# schematic.net
KiCad netlist of a schematic drawn in EAGLE
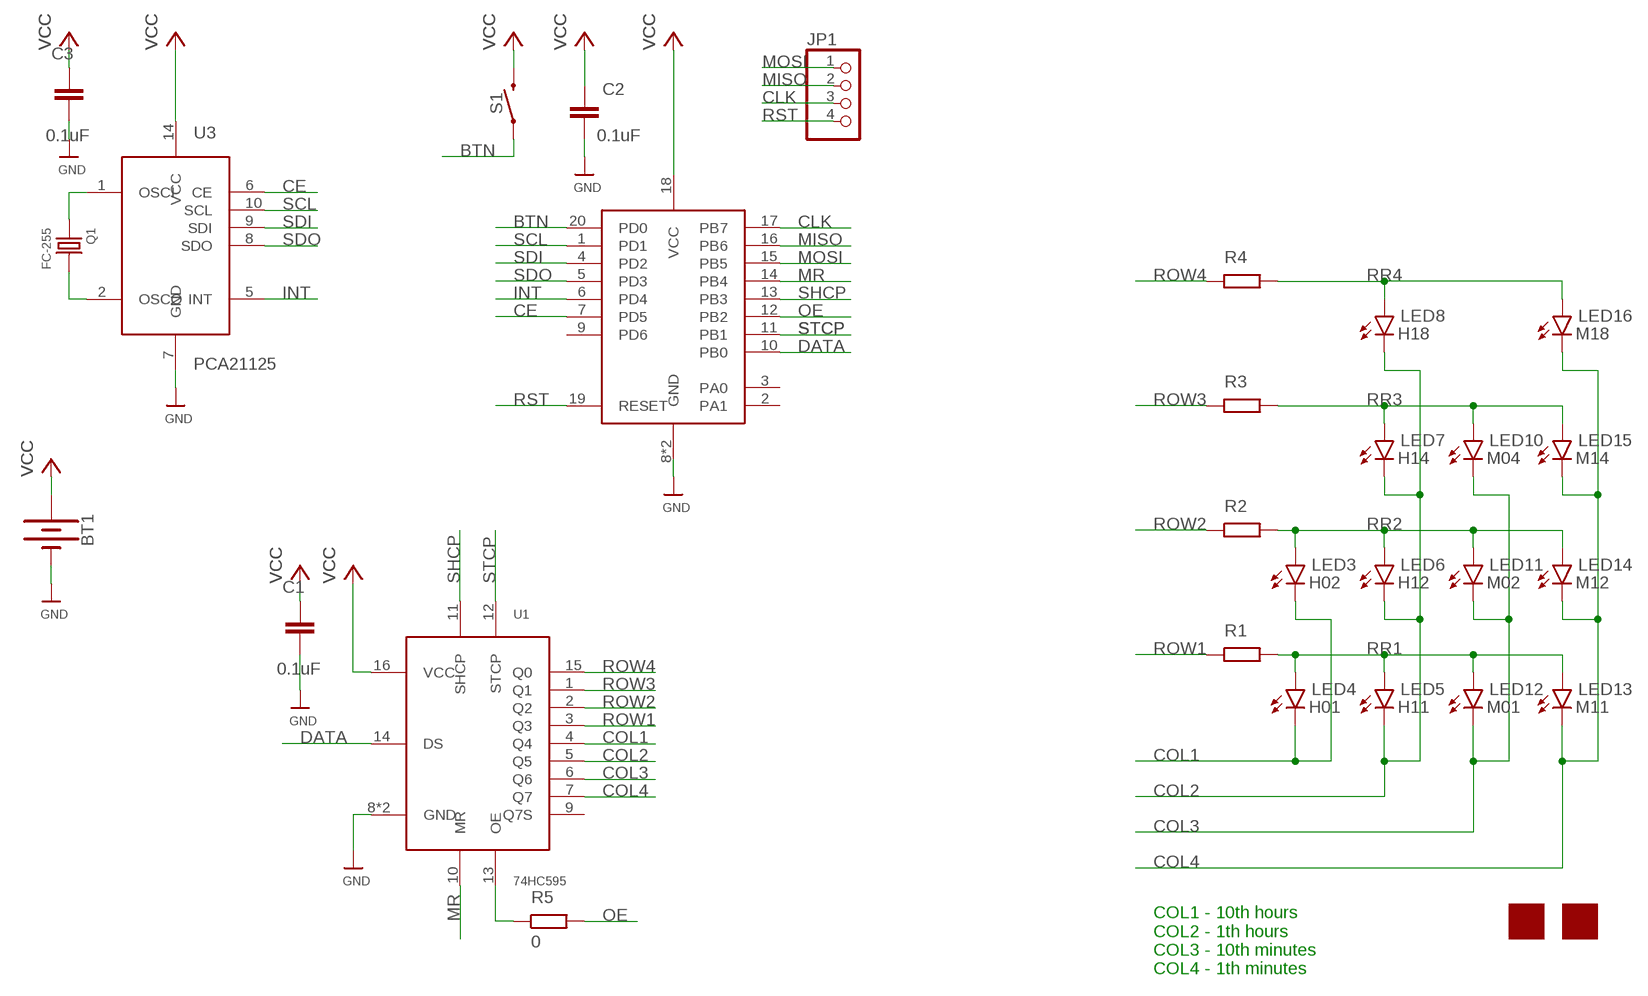
[diagram p0: schematic, sheet 1]

(export (version "E")
  (design (tool "Eeschema 10.0.6"))
  (components
    (comp (ref "BT1")
      (value "BATTERY-12MM_SMD")
      (footprint "eagle-import:BATTCON_12MM")
      (libsource (lib "eagle-import") (part "BATTERY-12MM_SMD"))
    )
    (comp (ref "C1")
      (value "0.1uF")
      (footprint "eagle-import:CAP_0402")
      (fields
        (field (name "DIGIKEY_PART_NUMBER") "311-2076-2-ND")
        (field (name "MANUFACTURER") "Yageo")
        (field (name "MPN") "CC0402CRNPO9BN1R0")
        (field (name "CREATED_BY") "PCBLayout.com")
      )
      (libsource (lib "eagle-import") (part "CC0402CRNPO9BN1R0"))
    )
    (comp (ref "C2")
      (value "0.1uF")
      (footprint "eagle-import:CAP_0402")
      (fields
        (field (name "DIGIKEY_PART_NUMBER") "311-2076-2-ND")
        (field (name "MANUFACTURER") "Yageo")
        (field (name "MPN") "CC0402CRNPO9BN1R0")
        (field (name "CREATED_BY") "PCBLayout.com")
      )
      (libsource (lib "eagle-import") (part "CC0402CRNPO9BN1R0"))
    )
    (comp (ref "C3")
      (value "0.1uF")
      (footprint "eagle-import:CAP_0402")
      (fields
        (field (name "DIGIKEY_PART_NUMBER") "311-2076-2-ND")
        (field (name "MANUFACTURER") "Yageo")
        (field (name "MPN") "CC0402CRNPO9BN1R0")
        (field (name "CREATED_BY") "PCBLayout.com")
      )
      (libsource (lib "eagle-import") (part "CC0402CRNPO9BN1R0"))
    )
    (comp (ref "IMG1")
      (value "IMAGE")
      (footprint "eagle-import:IMG6")
      (libsource (lib "eagle-import") (part "IMAGE"))
    )
    (comp (ref "IMG2")
      (value "SLOT")
      (footprint "eagle-import:SLOT")
      (libsource (lib "eagle-import") (part "SLOT"))
    )
    (comp (ref "JP1")
      (value "PINHD-1X4")
      (footprint "eagle-import:1X04")
      (libsource (lib "eagle-import") (part "PINHD-1X4"))
    )
    (comp (ref "LED3")
      (value "H02")
      (footprint "eagle-import:LG-T67K")
      (libsource (lib "eagle-import") (part "LG-T67K"))
    )
    (comp (ref "LED4")
      (value "H01")
      (footprint "eagle-import:LG-T67K")
      (libsource (lib "eagle-import") (part "LG-T67K"))
    )
    (comp (ref "LED5")
      (value "H11")
      (footprint "eagle-import:LG-T67K")
      (libsource (lib "eagle-import") (part "LG-T67K"))
    )
    (comp (ref "LED6")
      (value "H12")
      (footprint "eagle-import:LG-T67K")
      (libsource (lib "eagle-import") (part "LG-T67K"))
    )
    (comp (ref "LED7")
      (value "H14")
      (footprint "eagle-import:LG-T67K")
      (libsource (lib "eagle-import") (part "LG-T67K"))
    )
    (comp (ref "LED8")
      (value "H18")
      (footprint "eagle-import:LG-T67K")
      (libsource (lib "eagle-import") (part "LG-T67K"))
    )
    (comp (ref "LED10")
      (value "M04")
      (footprint "eagle-import:LG-T67K")
      (libsource (lib "eagle-import") (part "LG-T67K"))
    )
    (comp (ref "LED11")
      (value "M02")
      (footprint "eagle-import:LG-T67K")
      (libsource (lib "eagle-import") (part "LG-T67K"))
    )
    (comp (ref "LED12")
      (value "M01")
      (footprint "eagle-import:LG-T67K")
      (libsource (lib "eagle-import") (part "LG-T67K"))
    )
    (comp (ref "LED13")
      (value "M11")
      (footprint "eagle-import:LG-T67K")
      (libsource (lib "eagle-import") (part "LG-T67K"))
    )
    (comp (ref "LED14")
      (value "M12")
      (footprint "eagle-import:LG-T67K")
      (libsource (lib "eagle-import") (part "LG-T67K"))
    )
    (comp (ref "LED15")
      (value "M14")
      (footprint "eagle-import:LG-T67K")
      (libsource (lib "eagle-import") (part "LG-T67K"))
    )
    (comp (ref "LED16")
      (value "M18")
      (footprint "eagle-import:LG-T67K")
      (libsource (lib "eagle-import") (part "LG-T67K"))
    )
    (comp (ref "Q1")
      (value "FC-255")
      (footprint "eagle-import:FC-255")
      (libsource (lib "eagle-import") (part "FC-255"))
    )
    (comp (ref "R1")
      (value "R_CHIP-0402(1005-METRIC)")
      (footprint "eagle-import:RESC1005X40")
      (libsource (lib "eagle-import") (part "RCHIP-0402(1005-METRIC)_"))
    )
    (comp (ref "R2")
      (value "R_CHIP-0402(1005-METRIC)")
      (footprint "eagle-import:RESC1005X40")
      (libsource (lib "eagle-import") (part "RCHIP-0402(1005-METRIC)_"))
    )
    (comp (ref "R3")
      (value "R_CHIP-0402(1005-METRIC)")
      (footprint "eagle-import:RESC1005X40")
      (libsource (lib "eagle-import") (part "RCHIP-0402(1005-METRIC)_"))
    )
    (comp (ref "R4")
      (value "R_CHIP-0402(1005-METRIC)")
      (footprint "eagle-import:RESC1005X40")
      (libsource (lib "eagle-import") (part "RCHIP-0402(1005-METRIC)_"))
    )
    (comp (ref "R5")
      (value "0")
      (footprint "eagle-import:RESC1005X40")
      (libsource (lib "eagle-import") (part "RCHIP-0402(1005-METRIC)_"))
    )
    (comp (ref "S1")
      (value "MOMENTARY-SWITCH-SPST-SMD-6.2MM-TALL")
      (footprint "eagle-import:TACTILE_SWITCH_SMD_6.2MM_TALL")
      (libsource (lib "eagle-import") (part "MOMENTARY-SWITCH-SPST-SMD-6.2MM-TALL"))
    )
    (comp (ref "U1")
      (value "74HC595")
      (footprint "eagle-import:DHVQFN16")
      (libsource (lib "eagle-import") (part "74HC595"))
    )
    (comp (ref "U2")
      (value "ATTINY2313")
      (footprint "eagle-import:QFN20-.45MMPITCH")
      (libsource (lib "eagle-import") (part "ATTINY2313AQFN20-3X3"))
    )
    (comp (ref "U3")
      (value "PCA21125")
      (footprint "eagle-import:TSSOP14")
      (libsource (lib "eagle-import") (part "PCA21125"))
    )
  )
  (nets
    (net (code "1") (name "/BTN") (class "Default")
      (node (ref "S1") (pin "A2") (pinfunction "1_A2") (pintype "passive"))
      (node (ref "U2") (pin "20") (pinfunction "PD0_20") (pintype "bidirectional"))
    )
    (net (code "2") (name "/CE") (class "Default")
      (node (ref "U2") (pin "7") (pinfunction "PD5_7") (pintype "bidirectional"))
      (node (ref "U3") (pin "6") (pinfunction "CE_6") (pintype "bidirectional"))
    )
    (net (code "3") (name "/CLK") (class "Default")
      (node (ref "JP1") (pin "3") (pinfunction "3_3") (pintype "passive"))
      (node (ref "U2") (pin "17") (pinfunction "PB7_17") (pintype "bidirectional"))
    )
    (net (code "4") (name "/COL1") (class "Default")
      (node (ref "LED3") (pin "P$2") (pinfunction "C_P$2") (pintype "passive"))
      (node (ref "LED4") (pin "P$2") (pinfunction "C_P$2") (pintype "passive"))
      (node (ref "U1") (pin "4") (pinfunction "Q4_4") (pintype "bidirectional"))
    )
    (net (code "5") (name "/COL2") (class "Default")
      (node (ref "LED5") (pin "P$2") (pinfunction "C_P$2") (pintype "passive"))
      (node (ref "LED6") (pin "P$2") (pinfunction "C_P$2") (pintype "passive"))
      (node (ref "LED7") (pin "P$2") (pinfunction "C_P$2") (pintype "passive"))
      (node (ref "LED8") (pin "P$2") (pinfunction "C_P$2") (pintype "passive"))
      (node (ref "U1") (pin "5") (pinfunction "Q5_5") (pintype "bidirectional"))
    )
    (net (code "6") (name "/COL3") (class "Default")
      (node (ref "LED10") (pin "P$2") (pinfunction "C_P$2") (pintype "passive"))
      (node (ref "LED11") (pin "P$2") (pinfunction "C_P$2") (pintype "passive"))
      (node (ref "LED12") (pin "P$2") (pinfunction "C_P$2") (pintype "passive"))
      (node (ref "U1") (pin "6") (pinfunction "Q6_6") (pintype "bidirectional"))
    )
    (net (code "7") (name "/COL4") (class "Default")
      (node (ref "LED13") (pin "P$2") (pinfunction "C_P$2") (pintype "passive"))
      (node (ref "LED14") (pin "P$2") (pinfunction "C_P$2") (pintype "passive"))
      (node (ref "LED15") (pin "P$2") (pinfunction "C_P$2") (pintype "passive"))
      (node (ref "LED16") (pin "P$2") (pinfunction "C_P$2") (pintype "passive"))
      (node (ref "U1") (pin "7") (pinfunction "Q7_7") (pintype "bidirectional"))
    )
    (net (code "8") (name "/DATA") (class "Default")
      (node (ref "U1") (pin "14") (pinfunction "DS_14") (pintype "bidirectional"))
      (node (ref "U2") (pin "10") (pinfunction "PB0_10") (pintype "bidirectional"))
    )
    (net (code "9") (name "/INT") (class "Default")
      (node (ref "U2") (pin "6") (pinfunction "PD4_6") (pintype "bidirectional"))
      (node (ref "U3") (pin "5") (pinfunction "INT_5") (pintype "bidirectional"))
    )
    (net (code "10") (name "/MISO") (class "Default")
      (node (ref "JP1") (pin "2") (pinfunction "2_2") (pintype "passive"))
      (node (ref "U2") (pin "16") (pinfunction "PB6_16") (pintype "bidirectional"))
    )
    (net (code "11") (name "/MOSI") (class "Default")
      (node (ref "JP1") (pin "1") (pinfunction "1_1") (pintype "passive"))
      (node (ref "U2") (pin "15") (pinfunction "PB5_15") (pintype "bidirectional"))
    )
    (net (code "12") (name "/MR") (class "Default")
      (node (ref "U1") (pin "10") (pinfunction "MR_10") (pintype "bidirectional"))
      (node (ref "U2") (pin "14") (pinfunction "PB4_14") (pintype "bidirectional"))
    )
    (net (code "13") (name "/OE") (class "Default")
      (node (ref "R5") (pin "2") (pinfunction "2_2") (pintype "passive"))
      (node (ref "U2") (pin "12") (pinfunction "PB2_12") (pintype "bidirectional"))
    )
    (net (code "14") (name "/ROW1") (class "Default")
      (node (ref "R1") (pin "1") (pinfunction "1_1") (pintype "passive"))
      (node (ref "U1") (pin "3") (pinfunction "Q3_3") (pintype "bidirectional"))
    )
    (net (code "15") (name "/ROW2") (class "Default")
      (node (ref "R2") (pin "1") (pinfunction "1_1") (pintype "passive"))
      (node (ref "U1") (pin "2") (pinfunction "Q2_2") (pintype "bidirectional"))
    )
    (net (code "16") (name "/ROW3") (class "Default")
      (node (ref "R3") (pin "1") (pinfunction "1_1") (pintype "passive"))
      (node (ref "U1") (pin "1") (pinfunction "Q1_1") (pintype "bidirectional"))
    )
    (net (code "17") (name "/ROW4") (class "Default")
      (node (ref "R4") (pin "1") (pinfunction "1_1") (pintype "passive"))
      (node (ref "U1") (pin "15") (pinfunction "Q0_15") (pintype "bidirectional"))
    )
    (net (code "18") (name "/RR1") (class "Default")
      (node (ref "LED12") (pin "P$1") (pinfunction "A_P$1") (pintype "passive"))
      (node (ref "LED13") (pin "P$1") (pinfunction "A_P$1") (pintype "passive"))
      (node (ref "LED4") (pin "P$1") (pinfunction "A_P$1") (pintype "passive"))
      (node (ref "LED5") (pin "P$1") (pinfunction "A_P$1") (pintype "passive"))
      (node (ref "R1") (pin "2") (pinfunction "2_2") (pintype "passive"))
    )
    (net (code "19") (name "/RR2") (class "Default")
      (node (ref "LED11") (pin "P$1") (pinfunction "A_P$1") (pintype "passive"))
      (node (ref "LED14") (pin "P$1") (pinfunction "A_P$1") (pintype "passive"))
      (node (ref "LED3") (pin "P$1") (pinfunction "A_P$1") (pintype "passive"))
      (node (ref "LED6") (pin "P$1") (pinfunction "A_P$1") (pintype "passive"))
      (node (ref "R2") (pin "2") (pinfunction "2_2") (pintype "passive"))
    )
    (net (code "20") (name "/RR3") (class "Default")
      (node (ref "LED10") (pin "P$1") (pinfunction "A_P$1") (pintype "passive"))
      (node (ref "LED15") (pin "P$1") (pinfunction "A_P$1") (pintype "passive"))
      (node (ref "LED7") (pin "P$1") (pinfunction "A_P$1") (pintype "passive"))
      (node (ref "R3") (pin "2") (pinfunction "2_2") (pintype "passive"))
    )
    (net (code "21") (name "/RR4") (class "Default")
      (node (ref "LED16") (pin "P$1") (pinfunction "A_P$1") (pintype "passive"))
      (node (ref "LED8") (pin "P$1") (pinfunction "A_P$1") (pintype "passive"))
      (node (ref "R4") (pin "2") (pinfunction "2_2") (pintype "passive"))
    )
    (net (code "22") (name "/RST") (class "Default")
      (node (ref "JP1") (pin "4") (pinfunction "4_4") (pintype "passive"))
      (node (ref "U2") (pin "19") (pinfunction "RESET_19") (pintype "bidirectional"))
    )
    (net (code "23") (name "/SCL") (class "Default")
      (node (ref "U2") (pin "1") (pinfunction "PD1_1") (pintype "bidirectional"))
      (node (ref "U3") (pin "10") (pinfunction "SCL_10") (pintype "bidirectional"))
    )
    (net (code "24") (name "/SDI") (class "Default")
      (node (ref "U2") (pin "4") (pinfunction "PD2_4") (pintype "bidirectional"))
      (node (ref "U3") (pin "9") (pinfunction "SDI_9") (pintype "bidirectional"))
    )
    (net (code "25") (name "/SDO") (class "Default")
      (node (ref "U2") (pin "5") (pinfunction "PD3_5") (pintype "bidirectional"))
      (node (ref "U3") (pin "8") (pinfunction "SDO_8") (pintype "bidirectional"))
    )
    (net (code "26") (name "/SHCP") (class "Default")
      (node (ref "U1") (pin "11") (pinfunction "SHCP_11") (pintype "bidirectional"))
      (node (ref "U2") (pin "13") (pinfunction "PB3_13") (pintype "bidirectional"))
    )
    (net (code "27") (name "/STCP") (class "Default")
      (node (ref "U1") (pin "12") (pinfunction "STCP_12") (pintype "bidirectional"))
      (node (ref "U2") (pin "11") (pinfunction "PB1_11") (pintype "bidirectional"))
    )
    (net (code "28") (name "GND") (class "Default")
      (node (ref "BT1") (pin "GND") (pinfunction "-_GND") (pintype "power_in"))
      (node (ref "C1") (pin "2") (pinfunction "2_2") (pintype "passive"))
      (node (ref "C2") (pin "2") (pinfunction "2_2") (pintype "passive"))
      (node (ref "C3") (pin "2") (pinfunction "2_2") (pintype "passive"))
      (node (ref "U1") (pin "8") (pinfunction "GND_8") (pintype "bidirectional"))
      (node (ref "U1") (pin "PAD") (pinfunction "GND_PAD") (pintype "bidirectional"))
      (node (ref "U2") (pin "21") (pinfunction "GND_21") (pintype "bidirectional"))
      (node (ref "U2") (pin "8") (pinfunction "GND_8") (pintype "bidirectional"))
      (node (ref "U3") (pin "7") (pinfunction "GND_7") (pintype "bidirectional"))
    )
    (net (code "29") (name "Net-(Q1-1)") (class "Default")
      (node (ref "Q1") (pin "IN") (pinfunction "1_IN") (pintype "passive"))
      (node (ref "U3") (pin "1") (pinfunction "OSCI_1") (pintype "bidirectional"))
    )
    (net (code "30") (name "Net-(Q1-2)") (class "Default")
      (node (ref "Q1") (pin "OUT") (pinfunction "2_OUT") (pintype "passive"))
      (node (ref "U3") (pin "2") (pinfunction "OSCO_2") (pintype "bidirectional"))
    )
    (net (code "31") (name "Net-(U1-OE)") (class "Default")
      (node (ref "R5") (pin "1") (pinfunction "1_1") (pintype "passive"))
      (node (ref "U1") (pin "13") (pinfunction "OE_13") (pintype "bidirectional"))
    )
    (net (code "32") (name "VCC") (class "Default")
      (node (ref "BT1") (pin "PWR@1") (pinfunction "+_PWR@1") (pintype "power_in"))
      (node (ref "C1") (pin "1") (pinfunction "1_1") (pintype "passive"))
      (node (ref "C2") (pin "1") (pinfunction "1_1") (pintype "passive"))
      (node (ref "C3") (pin "1") (pinfunction "1_1") (pintype "passive"))
      (node (ref "S1") (pin "B2") (pinfunction "2_B2") (pintype "passive"))
      (node (ref "U1") (pin "16") (pinfunction "VCC_16") (pintype "bidirectional"))
      (node (ref "U2") (pin "18") (pinfunction "VCC_18") (pintype "bidirectional"))
      (node (ref "U3") (pin "14") (pinfunction "VCC_14") (pintype "bidirectional"))
    )
    (net (code "33") (name "unconnected-(U1-Q7S-Pad9)") (class "Default")
      (node (ref "U1") (pin "9") (pinfunction "Q7S_9") (pintype "bidirectional"))
    )
    (net (code "34") (name "unconnected-(U2-PA0-Pad3)") (class "Default")
      (node (ref "U2") (pin "3") (pinfunction "PA0_3") (pintype "bidirectional"))
    )
    (net (code "35") (name "unconnected-(U2-PA1-Pad2)") (class "Default")
      (node (ref "U2") (pin "2") (pinfunction "PA1_2") (pintype "bidirectional"))
    )
    (net (code "36") (name "unconnected-(U2-PD6-Pad9)") (class "Default")
      (node (ref "U2") (pin "9") (pinfunction "PD6_9") (pintype "bidirectional"))
    )
  )
)
